# Sheet1.net
KiCad netlist of a schematic drawn in Altium Designer
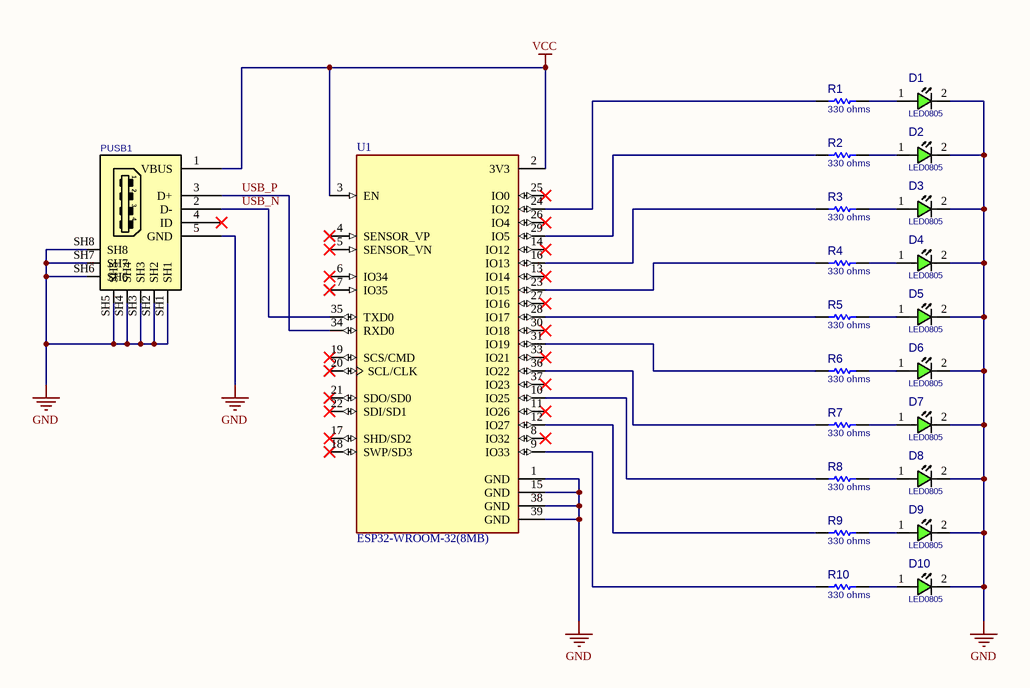
[diagram p0: Sheet1.SchDoc]

(export (version "E")
  (design (tool "Eeschema 10.0.6"))
  (components
    (comp (ref "D1")
      (value "LED0805")
      (footprint "LED0805")
      (description "LED, SMD, 0805")
      (fields (field (name "MANF") "MANF") (field (name "MANF_P#") "MANF_PART#"))
      (libsource (lib "led(diode)") (part "LED_SMD_0805"))
    )
    (comp (ref "D2")
      (value "LED0805")
      (footprint "LED0805")
      (description "LED, SMD, 0805")
      (fields (field (name "MANF") "MANF") (field (name "MANF_P#") "MANF_PART#"))
      (libsource (lib "led(diode)") (part "LED_SMD_0805"))
    )
    (comp (ref "D3")
      (value "LED0805")
      (footprint "LED0805")
      (description "LED, SMD, 0805")
      (fields (field (name "MANF") "MANF") (field (name "MANF_P#") "MANF_PART#"))
      (libsource (lib "led(diode)") (part "LED_SMD_0805"))
    )
    (comp (ref "D4")
      (value "LED0805")
      (footprint "LED0805")
      (description "LED, SMD, 0805")
      (fields (field (name "MANF") "MANF") (field (name "MANF_P#") "MANF_PART#"))
      (libsource (lib "led(diode)") (part "LED_SMD_0805"))
    )
    (comp (ref "D5")
      (value "LED0805")
      (footprint "LED0805")
      (description "LED, SMD, 0805")
      (fields (field (name "MANF") "MANF") (field (name "MANF_P#") "MANF_PART#"))
      (libsource (lib "led(diode)") (part "LED_SMD_0805"))
    )
    (comp (ref "D6")
      (value "LED0805")
      (footprint "LED0805")
      (description "LED, SMD, 0805")
      (fields (field (name "MANF") "MANF") (field (name "MANF_P#") "MANF_PART#"))
      (libsource (lib "led(diode)") (part "LED_SMD_0805"))
    )
    (comp (ref "D7")
      (value "LED0805")
      (footprint "LED0805")
      (description "LED, SMD, 0805")
      (fields (field (name "MANF") "MANF") (field (name "MANF_P#") "MANF_PART#"))
      (libsource (lib "led(diode)") (part "LED_SMD_0805"))
    )
    (comp (ref "D8")
      (value "LED0805")
      (footprint "LED0805")
      (description "LED, SMD, 0805")
      (fields (field (name "MANF") "MANF") (field (name "MANF_P#") "MANF_PART#"))
      (libsource (lib "led(diode)") (part "LED_SMD_0805"))
    )
    (comp (ref "D9")
      (value "LED0805")
      (footprint "LED0805")
      (description "LED, SMD, 0805")
      (fields (field (name "MANF") "MANF") (field (name "MANF_P#") "MANF_PART#"))
      (libsource (lib "led(diode)") (part "LED_SMD_0805"))
    )
    (comp (ref "D10")
      (value "LED0805")
      (footprint "LED0805")
      (description "LED, SMD, 0805")
      (fields (field (name "MANF") "MANF") (field (name "MANF_P#") "MANF_PART#"))
      (libsource (lib "led(diode)") (part "LED_SMD_0805"))
    )
    (comp (ref "PUSB1")
      (value "CONN_USB_MICROB")
      (footprint "USB_MICRO_B_BM_SHS")
      (description "CONN, USB, MICRO B, R/A, SMD, BOTTOM MOUNT")
      (fields (field (name "MANF_P#") "47346-0001") (field (name "MANF") "Molex"))
      (libsource (lib "conn_usb") (part "CONN_USB_MICRO_B_BM_SHS"))
    )
    (comp (ref "R1")
      (value "330 ohms")
      (footprint "R0805")
      (description "RESISTOR, SMD")
      (libsource (lib "passive_smd") (part "RES_SMD_0805"))
    )
    (comp (ref "R2")
      (value "330 ohms")
      (footprint "R0805")
      (description "RESISTOR, SMD")
      (libsource (lib "passive_smd") (part "RES_SMD_0805"))
    )
    (comp (ref "R3")
      (value "330 ohms")
      (footprint "R0805")
      (description "RESISTOR, SMD")
      (libsource (lib "passive_smd") (part "RES_SMD_0805"))
    )
    (comp (ref "R4")
      (value "330 ohms")
      (footprint "R0805")
      (description "RESISTOR, SMD")
      (libsource (lib "passive_smd") (part "RES_SMD_0805"))
    )
    (comp (ref "R5")
      (value "330 ohms")
      (footprint "R0805")
      (description "RESISTOR, SMD")
      (libsource (lib "passive_smd") (part "RES_SMD_0805"))
    )
    (comp (ref "R6")
      (value "330 ohms")
      (footprint "R0805")
      (description "RESISTOR, SMD")
      (libsource (lib "passive_smd") (part "RES_SMD_0805"))
    )
    (comp (ref "R7")
      (value "330 ohms")
      (footprint "R0805")
      (description "RESISTOR, SMD")
      (libsource (lib "passive_smd") (part "RES_SMD_0805"))
    )
    (comp (ref "R8")
      (value "330 ohms")
      (footprint "R0805")
      (description "RESISTOR, SMD")
      (libsource (lib "passive_smd") (part "RES_SMD_0805"))
    )
    (comp (ref "R9")
      (value "330 ohms")
      (footprint "R0805")
      (description "RESISTOR, SMD")
      (libsource (lib "passive_smd") (part "RES_SMD_0805"))
    )
    (comp (ref "R10")
      (value "330 ohms")
      (footprint "R0805")
      (description "RESISTOR, SMD")
      (libsource (lib "passive_smd") (part "RES_SMD_0805"))
    )
    (comp (ref "U1")
      (value "ESP32-WROOM-32(8MB)")
      (footprint "MODULE_ESP32-WROOM-32(8MB)")
      (fields (field (name "MF") "Espressif Systems") (field (name "MP") "ESP32-WROOM-32 (8MB)"))
      (libsource (lib "ESP32-WROOM-32_8MB_") (part "ESP32-WROOM-32(8MB)"))
    )
  )
  (nets
    (net (code "1") (name "/USB_N") (class "Default")
      (node (ref "PUSB1") (pin "2") (pinfunction "D-_2") (pintype "passive"))
      (node (ref "U1") (pin "35") (pinfunction "TXD0_35") (pintype "bidirectional"))
    )
    (net (code "2") (name "/USB_P") (class "Default")
      (node (ref "PUSB1") (pin "3") (pinfunction "D+_3") (pintype "passive"))
      (node (ref "U1") (pin "34") (pinfunction "RXD0_34") (pintype "bidirectional"))
    )
    (net (code "3") (name "GND") (class "Default")
      (node (ref "D1") (pin "2") (pinfunction "CATHODE_2") (pintype "passive"))
      (node (ref "D10") (pin "2") (pinfunction "CATHODE_2") (pintype "passive"))
      (node (ref "D2") (pin "2") (pinfunction "CATHODE_2") (pintype "passive"))
      (node (ref "D3") (pin "2") (pinfunction "CATHODE_2") (pintype "passive"))
      (node (ref "D4") (pin "2") (pinfunction "CATHODE_2") (pintype "passive"))
      (node (ref "D5") (pin "2") (pinfunction "CATHODE_2") (pintype "passive"))
      (node (ref "D6") (pin "2") (pinfunction "CATHODE_2") (pintype "passive"))
      (node (ref "D7") (pin "2") (pinfunction "CATHODE_2") (pintype "passive"))
      (node (ref "D8") (pin "2") (pinfunction "CATHODE_2") (pintype "passive"))
      (node (ref "D9") (pin "2") (pinfunction "CATHODE_2") (pintype "passive"))
      (node (ref "PUSB1") (pin "5") (pinfunction "GND_5") (pintype "power_in"))
      (node (ref "PUSB1") (pin "SH1") (pinfunction "SH1_SH1") (pintype "passive"))
      (node (ref "PUSB1") (pin "SH2") (pinfunction "SH2_SH2") (pintype "passive"))
      (node (ref "PUSB1") (pin "SH3") (pinfunction "SH3_SH3") (pintype "passive"))
      (node (ref "PUSB1") (pin "SH4") (pinfunction "SH4_SH4") (pintype "passive"))
      (node (ref "PUSB1") (pin "SH5") (pinfunction "SH5_SH5") (pintype "passive"))
      (node (ref "PUSB1") (pin "SH6") (pinfunction "SH6_SH6") (pintype "passive"))
      (node (ref "PUSB1") (pin "SH7") (pinfunction "SH7_SH7") (pintype "passive"))
      (node (ref "PUSB1") (pin "SH8") (pinfunction "SH8_SH8") (pintype "passive"))
      (node (ref "U1") (pin "1") (pinfunction "GND_1") (pintype "power_in"))
      (node (ref "U1") (pin "15") (pinfunction "GND_15") (pintype "power_in"))
      (node (ref "U1") (pin "38") (pinfunction "GND_38") (pintype "power_in"))
      (node (ref "U1") (pin "39") (pinfunction "GND_39") (pintype "power_in"))
    )
    (net (code "4") (name "Net-(D1-ANODE)") (class "Default")
      (node (ref "D1") (pin "1") (pinfunction "ANODE_1") (pintype "passive"))
      (node (ref "R1") (pin "2") (pinfunction "2_2") (pintype "passive"))
    )
    (net (code "5") (name "Net-(D2-ANODE)") (class "Default")
      (node (ref "D2") (pin "1") (pinfunction "ANODE_1") (pintype "passive"))
      (node (ref "R2") (pin "2") (pinfunction "2_2") (pintype "passive"))
    )
    (net (code "6") (name "Net-(D3-ANODE)") (class "Default")
      (node (ref "D3") (pin "1") (pinfunction "ANODE_1") (pintype "passive"))
      (node (ref "R3") (pin "2") (pinfunction "2_2") (pintype "passive"))
    )
    (net (code "7") (name "Net-(D4-ANODE)") (class "Default")
      (node (ref "D4") (pin "1") (pinfunction "ANODE_1") (pintype "passive"))
      (node (ref "R4") (pin "2") (pinfunction "2_2") (pintype "passive"))
    )
    (net (code "8") (name "Net-(D5-ANODE)") (class "Default")
      (node (ref "D5") (pin "1") (pinfunction "ANODE_1") (pintype "passive"))
      (node (ref "R5") (pin "2") (pinfunction "2_2") (pintype "passive"))
    )
    (net (code "9") (name "Net-(D6-ANODE)") (class "Default")
      (node (ref "D6") (pin "1") (pinfunction "ANODE_1") (pintype "passive"))
      (node (ref "R6") (pin "2") (pinfunction "2_2") (pintype "passive"))
    )
    (net (code "10") (name "Net-(D7-ANODE)") (class "Default")
      (node (ref "D7") (pin "1") (pinfunction "ANODE_1") (pintype "passive"))
      (node (ref "R7") (pin "2") (pinfunction "2_2") (pintype "passive"))
    )
    (net (code "11") (name "Net-(D8-ANODE)") (class "Default")
      (node (ref "D8") (pin "1") (pinfunction "ANODE_1") (pintype "passive"))
      (node (ref "R8") (pin "2") (pinfunction "2_2") (pintype "passive"))
    )
    (net (code "12") (name "Net-(D9-ANODE)") (class "Default")
      (node (ref "D9") (pin "1") (pinfunction "ANODE_1") (pintype "passive"))
      (node (ref "R9") (pin "2") (pinfunction "2_2") (pintype "passive"))
    )
    (net (code "13") (name "Net-(D10-ANODE)") (class "Default")
      (node (ref "D10") (pin "1") (pinfunction "ANODE_1") (pintype "passive"))
      (node (ref "R10") (pin "2") (pinfunction "2_2") (pintype "passive"))
    )
    (net (code "14") (name "Net-(U1-IO2)") (class "Default")
      (node (ref "R1") (pin "1") (pinfunction "1_1") (pintype "passive"))
      (node (ref "U1") (pin "24") (pinfunction "IO2_24") (pintype "bidirectional"))
    )
    (net (code "15") (name "Net-(U1-IO5)") (class "Default")
      (node (ref "R2") (pin "1") (pinfunction "1_1") (pintype "passive"))
      (node (ref "U1") (pin "29") (pinfunction "IO5_29") (pintype "bidirectional"))
    )
    (net (code "16") (name "Net-(U1-IO13)") (class "Default")
      (node (ref "R3") (pin "1") (pinfunction "1_1") (pintype "passive"))
      (node (ref "U1") (pin "16") (pinfunction "IO13_16") (pintype "bidirectional"))
    )
    (net (code "17") (name "Net-(U1-IO15)") (class "Default")
      (node (ref "R4") (pin "1") (pinfunction "1_1") (pintype "passive"))
      (node (ref "U1") (pin "23") (pinfunction "IO15_23") (pintype "bidirectional"))
    )
    (net (code "18") (name "Net-(U1-IO17)") (class "Default")
      (node (ref "R5") (pin "1") (pinfunction "1_1") (pintype "passive"))
      (node (ref "U1") (pin "28") (pinfunction "IO17_28") (pintype "bidirectional"))
    )
    (net (code "19") (name "Net-(U1-IO19)") (class "Default")
      (node (ref "R6") (pin "1") (pinfunction "1_1") (pintype "passive"))
      (node (ref "U1") (pin "31") (pinfunction "IO19_31") (pintype "bidirectional"))
    )
    (net (code "20") (name "Net-(U1-IO22)") (class "Default")
      (node (ref "R7") (pin "1") (pinfunction "1_1") (pintype "passive"))
      (node (ref "U1") (pin "36") (pinfunction "IO22_36") (pintype "bidirectional"))
    )
    (net (code "21") (name "Net-(U1-IO25)") (class "Default")
      (node (ref "R8") (pin "1") (pinfunction "1_1") (pintype "passive"))
      (node (ref "U1") (pin "10") (pinfunction "IO25_10") (pintype "bidirectional"))
    )
    (net (code "22") (name "Net-(U1-IO27)") (class "Default")
      (node (ref "R9") (pin "1") (pinfunction "1_1") (pintype "passive"))
      (node (ref "U1") (pin "12") (pinfunction "IO27_12") (pintype "bidirectional"))
    )
    (net (code "23") (name "Net-(U1-IO33)") (class "Default")
      (node (ref "R10") (pin "1") (pinfunction "1_1") (pintype "passive"))
      (node (ref "U1") (pin "9") (pinfunction "IO33_9") (pintype "bidirectional"))
    )
    (net (code "24") (name "VCC") (class "Default")
      (node (ref "PUSB1") (pin "1") (pinfunction "VBUS_1") (pintype "power_in"))
      (node (ref "U1") (pin "2") (pinfunction "3V3_2") (pintype "power_in"))
      (node (ref "U1") (pin "3") (pinfunction "EN_3") (pintype "input"))
    )
    (net (code "25") (name "unconnected-(PUSB1-ID-Pad4)") (class "Default")
      (node (ref "PUSB1") (pin "4") (pinfunction "ID_4") (pintype "power_in+no_connect"))
    )
    (net (code "26") (name "unconnected-(U1-IO0-Pad25)") (class "Default")
      (node (ref "U1") (pin "25") (pinfunction "IO0_25") (pintype "bidirectional+no_connect"))
    )
    (net (code "27") (name "unconnected-(U1-IO4-Pad26)") (class "Default")
      (node (ref "U1") (pin "26") (pinfunction "IO4_26") (pintype "bidirectional+no_connect"))
    )
    (net (code "28") (name "unconnected-(U1-IO12-Pad14)") (class "Default")
      (node (ref "U1") (pin "14") (pinfunction "IO12_14") (pintype "bidirectional+no_connect"))
    )
    (net (code "29") (name "unconnected-(U1-IO14-Pad13)") (class "Default")
      (node (ref "U1") (pin "13") (pinfunction "IO14_13") (pintype "bidirectional+no_connect"))
    )
    (net (code "30") (name "unconnected-(U1-IO16-Pad27)") (class "Default")
      (node (ref "U1") (pin "27") (pinfunction "IO16_27") (pintype "bidirectional+no_connect"))
    )
    (net (code "31") (name "unconnected-(U1-IO18-Pad30)") (class "Default")
      (node (ref "U1") (pin "30") (pinfunction "IO18_30") (pintype "bidirectional+no_connect"))
    )
    (net (code "32") (name "unconnected-(U1-IO21-Pad33)") (class "Default")
      (node (ref "U1") (pin "33") (pinfunction "IO21_33") (pintype "bidirectional+no_connect"))
    )
    (net (code "33") (name "unconnected-(U1-IO23-Pad37)") (class "Default")
      (node (ref "U1") (pin "37") (pinfunction "IO23_37") (pintype "bidirectional+no_connect"))
    )
    (net (code "34") (name "unconnected-(U1-IO26-Pad11)") (class "Default")
      (node (ref "U1") (pin "11") (pinfunction "IO26_11") (pintype "bidirectional+no_connect"))
    )
    (net (code "35") (name "unconnected-(U1-IO32-Pad8)") (class "Default")
      (node (ref "U1") (pin "8") (pinfunction "IO32_8") (pintype "bidirectional+no_connect"))
    )
    (net (code "36") (name "unconnected-(U1-IO34-Pad6)") (class "Default")
      (node (ref "U1") (pin "6") (pinfunction "IO34_6") (pintype "input+no_connect"))
    )
    (net (code "37") (name "unconnected-(U1-IO35-Pad7)") (class "Default")
      (node (ref "U1") (pin "7") (pinfunction "IO35_7") (pintype "input+no_connect"))
    )
    (net (code "38") (name "unconnected-(U1-SCL{slash}CLK-Pad20)") (class "Default")
      (node (ref "U1") (pin "20") (pinfunction "SCL/CLK_20") (pintype "bidirectional+no_connect"))
    )
    (net (code "39") (name "unconnected-(U1-SCS{slash}CMD-Pad19)") (class "Default")
      (node (ref "U1") (pin "19") (pinfunction "SCS/CMD_19") (pintype "bidirectional+no_connect"))
    )
    (net (code "40") (name "unconnected-(U1-SDI{slash}SD1-Pad22)") (class "Default")
      (node (ref "U1") (pin "22") (pinfunction "SDI/SD1_22") (pintype "bidirectional+no_connect"))
    )
    (net (code "41") (name "unconnected-(U1-SDO{slash}SD0-Pad21)") (class "Default")
      (node (ref "U1") (pin "21") (pinfunction "SDO/SD0_21") (pintype "bidirectional+no_connect"))
    )
    (net (code "42") (name "unconnected-(U1-SENSOR_VN-Pad5)") (class "Default")
      (node (ref "U1") (pin "5") (pinfunction "SENSOR_VN_5") (pintype "input+no_connect"))
    )
    (net (code "43") (name "unconnected-(U1-SENSOR_VP-Pad4)") (class "Default")
      (node (ref "U1") (pin "4") (pinfunction "SENSOR_VP_4") (pintype "input+no_connect"))
    )
    (net (code "44") (name "unconnected-(U1-SHD{slash}SD2-Pad17)") (class "Default")
      (node (ref "U1") (pin "17") (pinfunction "SHD/SD2_17") (pintype "bidirectional+no_connect"))
    )
    (net (code "45") (name "unconnected-(U1-SWP{slash}SD3-Pad18)") (class "Default")
      (node (ref "U1") (pin "18") (pinfunction "SWP/SD3_18") (pintype "bidirectional+no_connect"))
    )
  )
)
